# Project.net
KiCad netlist of a schematic drawn in EasyEDA Pro
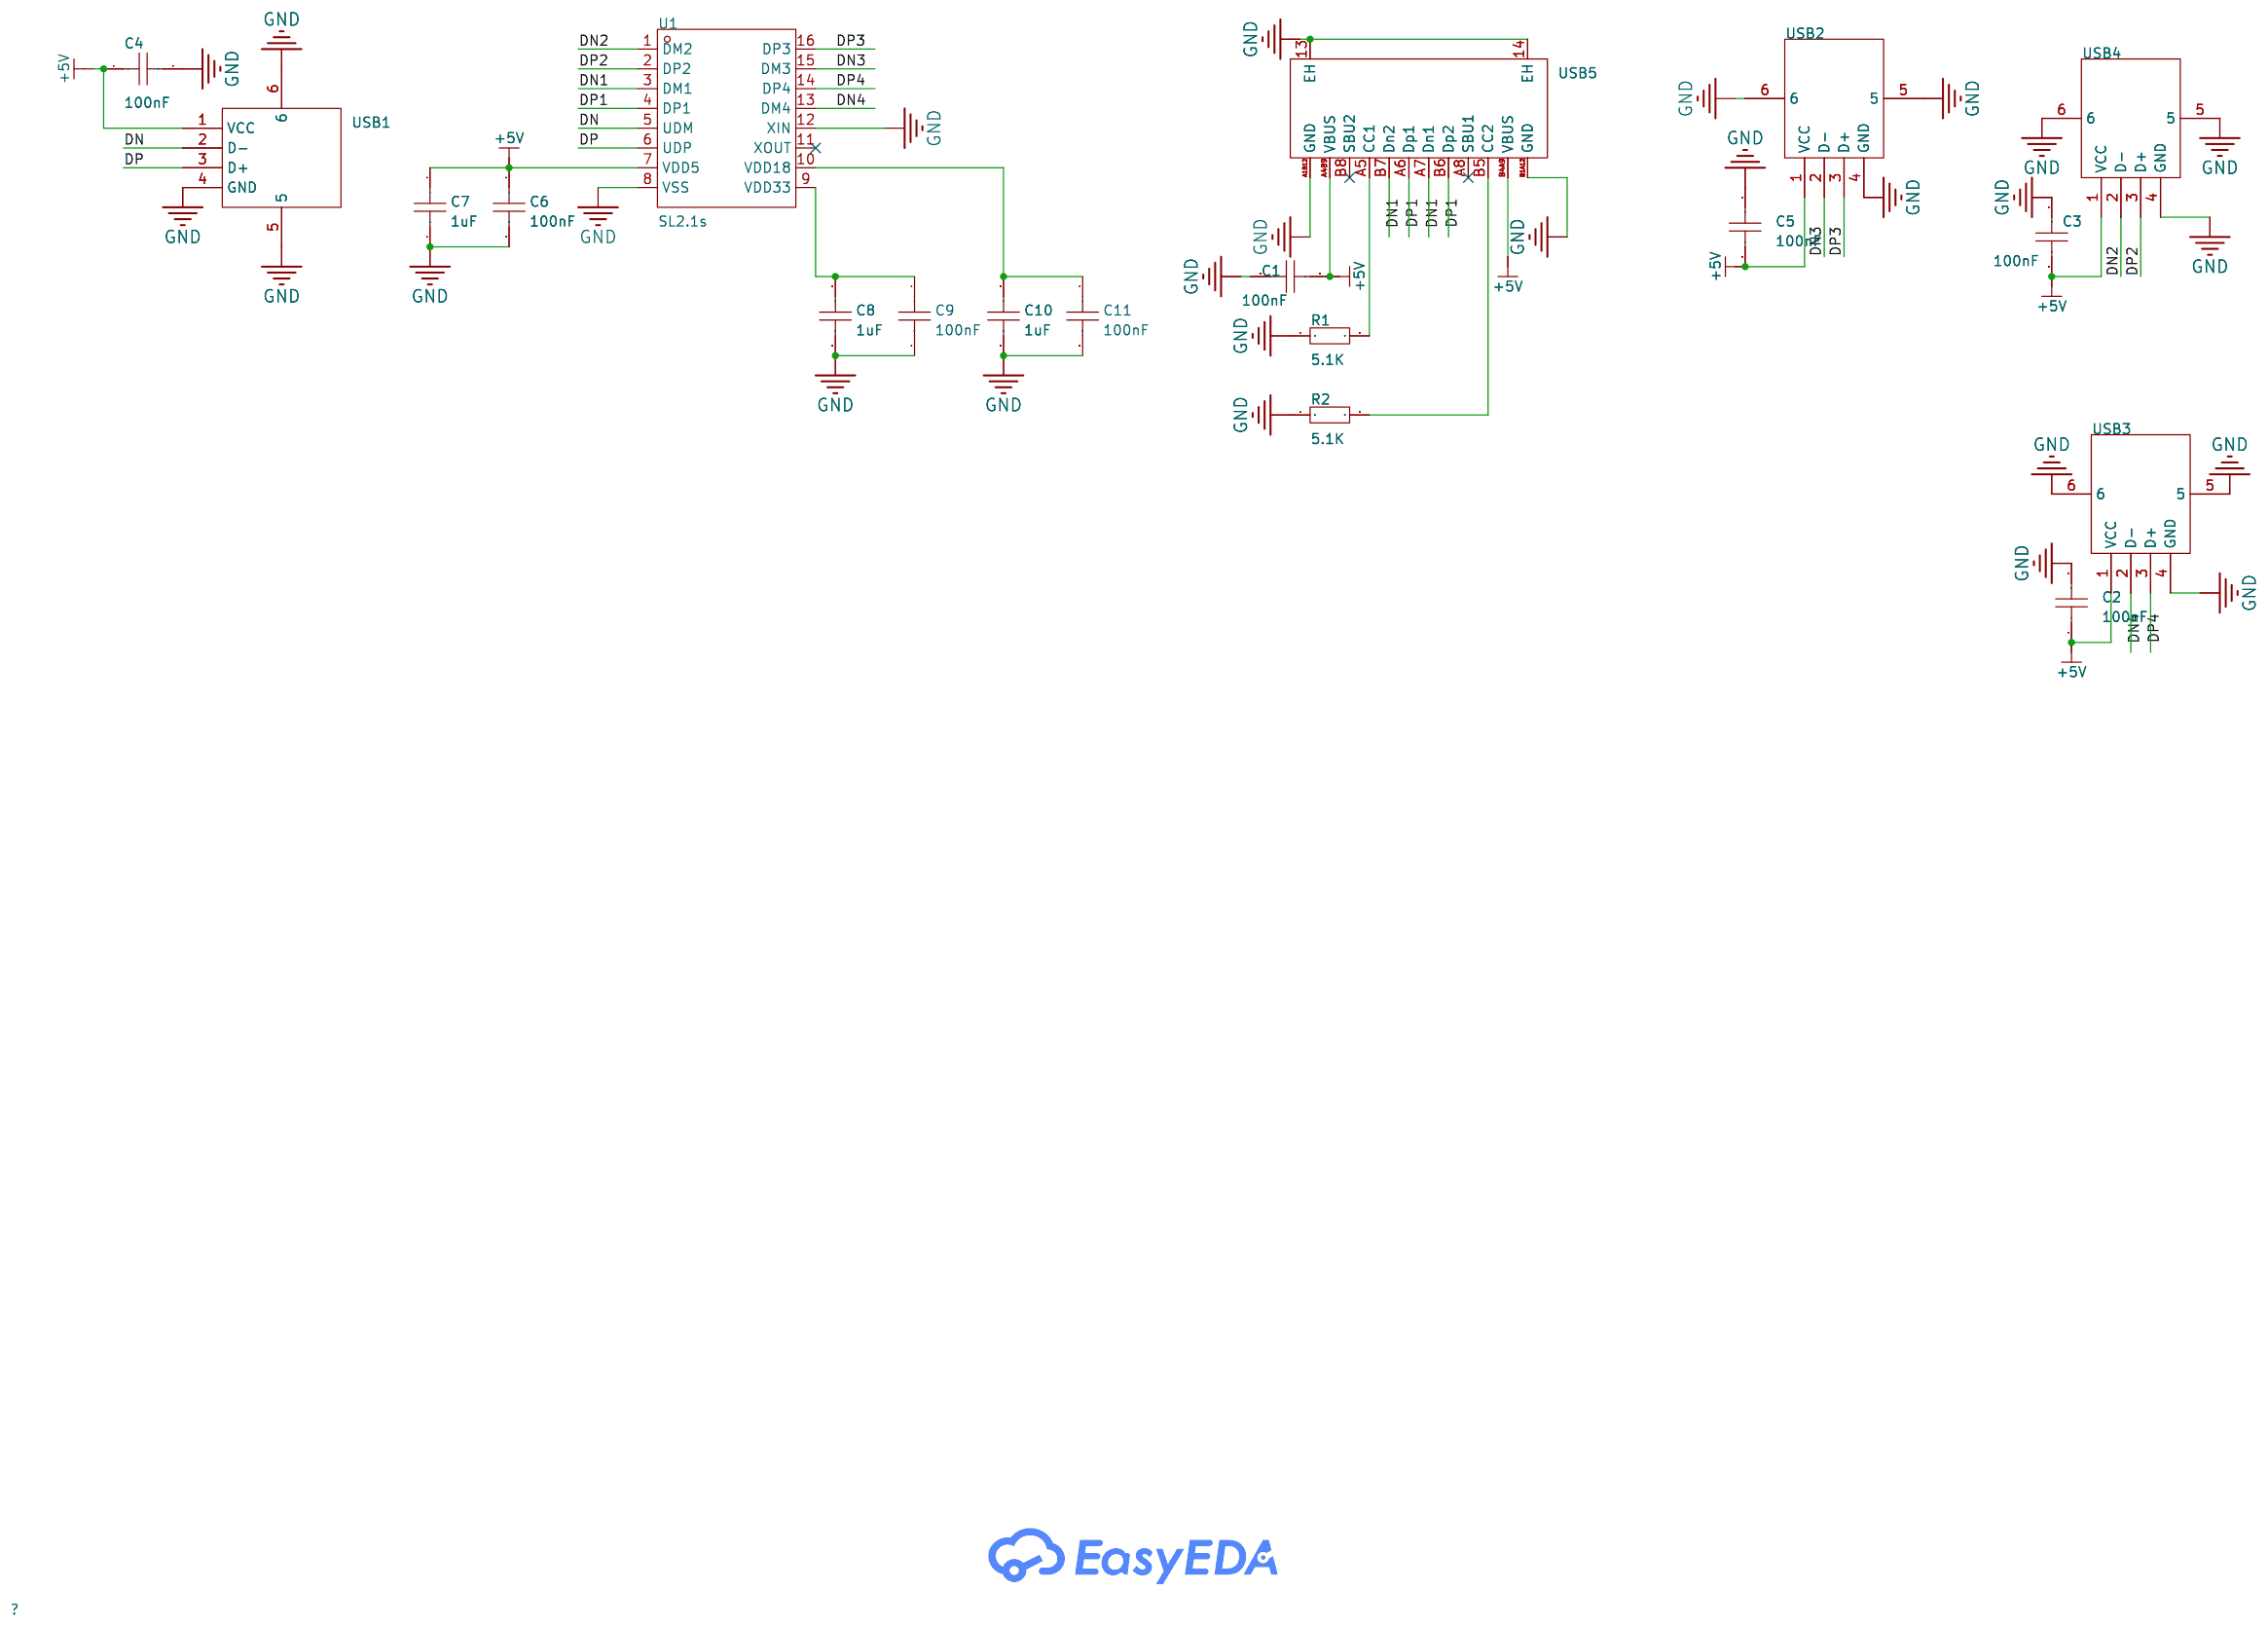
[diagram p0: schematic sheet]

(export (version "E")
  (design (tool "Eeschema 10.0.6"))
  (components
    (comp (ref "C1")
      (value "100nF")
      (footprint "easyedapro:C0603")
      (libsource (lib "easyedapro") (part "CAP"))
    )
    (comp (ref "C2")
      (value "100nF")
      (footprint "easyedapro:C0603")
      (libsource (lib "easyedapro") (part "CAP"))
    )
    (comp (ref "C3")
      (value "100nF")
      (footprint "easyedapro:C0603")
      (libsource (lib "easyedapro") (part "CAP"))
    )
    (comp (ref "C4")
      (value "100nF")
      (footprint "easyedapro:C0603")
      (libsource (lib "easyedapro") (part "CAP"))
    )
    (comp (ref "C5")
      (value "100nF")
      (footprint "easyedapro:C0603")
      (libsource (lib "easyedapro") (part "CAP"))
    )
    (comp (ref "C6")
      (value "100nF")
      (footprint "easyedapro:C0603")
      (libsource (lib "easyedapro") (part "CAP"))
    )
    (comp (ref "C7") (value "1uF") (footprint "easyedapro:C0603") (libsource (lib "easyedapro") (part "CAP")))
    (comp (ref "C8") (value "1uF") (footprint "easyedapro:C0603") (libsource (lib "easyedapro") (part "CAP")))
    (comp (ref "C9")
      (value "100nF")
      (footprint "easyedapro:C0603")
      (libsource (lib "easyedapro") (part "CAP"))
    )
    (comp (ref "C10")
      (value "1uF")
      (footprint "easyedapro:C0603")
      (libsource (lib "easyedapro") (part "CAP"))
    )
    (comp (ref "C11")
      (value "100nF")
      (footprint "easyedapro:C0603")
      (libsource (lib "easyedapro") (part "CAP"))
    )
    (comp (ref "R1")
      (value "5.1K")
      (footprint "easyedapro:R0603")
      (libsource (lib "easyedapro") (part "Res"))
    )
    (comp (ref "R2")
      (value "5.1K")
      (footprint "easyedapro:R0603")
      (libsource (lib "easyedapro") (part "Res"))
    )
    (comp (ref "U1")
      (value "SL2.1s")
      (footprint "easyedapro:SSOP-16_L4.6-W2.6-P0.53-LS4.0-BL")
      (fields (field (name "Manufacturer") "CoreChips(和芯润德)"))
      (libsource (lib "easyedapro") (part "SL2.1S"))
    )
    (comp (ref "USB1")
      (value "10.0 QHHTZB6.3")
      (footprint "easyedapro:USB-A-TH_10.0QHHTZB6.3")
      (fields (field (name "Manufacturer") "SHOU HAN(首韩)"))
      (libsource (lib "easyedapro") (part "10.0 QHHTZB6.3"))
    )
    (comp (ref "USB2")
      (value "10.0 QHHTZB6.3")
      (footprint "easyedapro:USB-A-TH_10.0QHHTZB6.3")
      (fields (field (name "Manufacturer") "SHOU HAN(首韩)"))
      (libsource (lib "easyedapro") (part "10.0 QHHTZB6.3"))
    )
    (comp (ref "USB3")
      (value "10.0 QHHTZB6.3")
      (footprint "easyedapro:USB-A-TH_10.0QHHTZB6.3")
      (fields (field (name "Manufacturer") "SHOU HAN(首韩)"))
      (libsource (lib "easyedapro") (part "10.0 QHHTZB6.3"))
    )
    (comp (ref "USB4")
      (value "10.0 QHHTZB6.3")
      (footprint "easyedapro:USB-A-TH_10.0QHHTZB6.3")
      (fields (field (name "Manufacturer") "SHOU HAN(首韩)"))
      (libsource (lib "easyedapro") (part "10.0 QHHTZB6.3"))
    )
    (comp (ref "USB5")
      (value "TYPE-C 16PIN 2MD(073)")
      (footprint "easyedapro:USB-C-SMD_TYPE-C-16PIN-2MD-073")
      (fields (field (name "Manufacturer") "SHOU HAN(首韩)"))
      (libsource (lib "easyedapro") (part "TYPE-C 16PIN 2MD(073)"))
    )
  )
  (nets
    (net (code "1") (name "+5V") (class "Default")
      (node (ref "C1") (pin "1") (pinfunction "1_1") (pintype "input"))
      (node (ref "C2") (pin "1") (pinfunction "1_1") (pintype "input"))
      (node (ref "C3") (pin "2") (pinfunction "2_2") (pintype "input"))
      (node (ref "C4") (pin "1") (pinfunction "1_1") (pintype "input"))
      (node (ref "C5") (pin "2") (pinfunction "2_2") (pintype "input"))
      (node (ref "C6") (pin "1") (pinfunction "1_1") (pintype "input"))
      (node (ref "C7") (pin "1") (pinfunction "1_1") (pintype "input"))
      (node (ref "U1") (pin "7") (pinfunction "VDD5_7") (pintype "unspecified"))
      (node (ref "USB1") (pin "1") (pinfunction "VCC_1") (pintype "unspecified"))
      (node (ref "USB2") (pin "1") (pinfunction "VCC_1") (pintype "unspecified"))
      (node (ref "USB3") (pin "1") (pinfunction "VCC_1") (pintype "unspecified"))
      (node (ref "USB4") (pin "1") (pinfunction "VCC_1") (pintype "unspecified"))
      (node (ref "USB5") (pin "A4B9") (pinfunction "VBUS_A4B9") (pintype "unspecified"))
      (node (ref "USB5") (pin "B4A9") (pinfunction "VBUS_B4A9") (pintype "unspecified"))
    )
    (net (code "2") (name "/DN") (class "Default")
      (node (ref "U1") (pin "5") (pinfunction "UDM_5") (pintype "unspecified"))
      (node (ref "USB1") (pin "2") (pinfunction "D-_2") (pintype "unspecified"))
    )
    (net (code "3") (name "/DN1") (class "Default")
      (node (ref "U1") (pin "3") (pinfunction "DM1_3") (pintype "unspecified"))
      (node (ref "USB5") (pin "A7") (pinfunction "Dn1_A7") (pintype "unspecified"))
      (node (ref "USB5") (pin "B7") (pinfunction "Dn2_B7") (pintype "unspecified"))
    )
    (net (code "4") (name "/DN2") (class "Default")
      (node (ref "U1") (pin "1") (pinfunction "DM2_1") (pintype "unspecified"))
      (node (ref "USB4") (pin "2") (pinfunction "D-_2") (pintype "unspecified"))
    )
    (net (code "5") (name "/DN3") (class "Default")
      (node (ref "U1") (pin "15") (pinfunction "DM3_15") (pintype "unspecified"))
      (node (ref "USB2") (pin "2") (pinfunction "D-_2") (pintype "unspecified"))
    )
    (net (code "6") (name "/DN4") (class "Default")
      (node (ref "U1") (pin "13") (pinfunction "DM4_13") (pintype "unspecified"))
      (node (ref "USB3") (pin "2") (pinfunction "D-_2") (pintype "unspecified"))
    )
    (net (code "7") (name "/DP") (class "Default")
      (node (ref "U1") (pin "6") (pinfunction "UDP_6") (pintype "unspecified"))
      (node (ref "USB1") (pin "3") (pinfunction "D+_3") (pintype "unspecified"))
    )
    (net (code "8") (name "/DP1") (class "Default")
      (node (ref "U1") (pin "4") (pinfunction "DP1_4") (pintype "unspecified"))
      (node (ref "USB5") (pin "A6") (pinfunction "Dp1_A6") (pintype "unspecified"))
      (node (ref "USB5") (pin "B6") (pinfunction "Dp2_B6") (pintype "unspecified"))
    )
    (net (code "9") (name "/DP2") (class "Default")
      (node (ref "U1") (pin "2") (pinfunction "DP2_2") (pintype "unspecified"))
      (node (ref "USB4") (pin "3") (pinfunction "D+_3") (pintype "unspecified"))
    )
    (net (code "10") (name "/DP3") (class "Default")
      (node (ref "U1") (pin "16") (pinfunction "DP3_16") (pintype "unspecified"))
      (node (ref "USB2") (pin "3") (pinfunction "D+_3") (pintype "unspecified"))
    )
    (net (code "11") (name "/DP4") (class "Default")
      (node (ref "U1") (pin "14") (pinfunction "DP4_14") (pintype "unspecified"))
      (node (ref "USB3") (pin "3") (pinfunction "D+_3") (pintype "unspecified"))
    )
    (net (code "12") (name "GND") (class "Default")
      (node (ref "C1") (pin "2") (pinfunction "2_2") (pintype "input"))
      (node (ref "C10") (pin "2") (pinfunction "2_2") (pintype "input"))
      (node (ref "C11") (pin "2") (pinfunction "2_2") (pintype "input"))
      (node (ref "C2") (pin "2") (pinfunction "2_2") (pintype "input"))
      (node (ref "C3") (pin "1") (pinfunction "1_1") (pintype "input"))
      (node (ref "C4") (pin "2") (pinfunction "2_2") (pintype "input"))
      (node (ref "C5") (pin "1") (pinfunction "1_1") (pintype "input"))
      (node (ref "C6") (pin "2") (pinfunction "2_2") (pintype "input"))
      (node (ref "C7") (pin "2") (pinfunction "2_2") (pintype "input"))
      (node (ref "C8") (pin "2") (pinfunction "2_2") (pintype "input"))
      (node (ref "C9") (pin "2") (pinfunction "2_2") (pintype "input"))
      (node (ref "R1") (pin "1") (pinfunction "1_1") (pintype "input"))
      (node (ref "R2") (pin "1") (pinfunction "1_1") (pintype "input"))
      (node (ref "U1") (pin "12") (pinfunction "XIN_12") (pintype "unspecified"))
      (node (ref "U1") (pin "8") (pinfunction "VSS_8") (pintype "unspecified"))
      (node (ref "USB1") (pin "4") (pinfunction "GND_4") (pintype "unspecified"))
      (node (ref "USB1") (pin "5") (pinfunction "5_5") (pintype "unspecified"))
      (node (ref "USB1") (pin "6") (pinfunction "6_6") (pintype "unspecified"))
      (node (ref "USB2") (pin "4") (pinfunction "GND_4") (pintype "unspecified"))
      (node (ref "USB2") (pin "5") (pinfunction "5_5") (pintype "unspecified"))
      (node (ref "USB2") (pin "6") (pinfunction "6_6") (pintype "unspecified"))
      (node (ref "USB3") (pin "4") (pinfunction "GND_4") (pintype "unspecified"))
      (node (ref "USB3") (pin "5") (pinfunction "5_5") (pintype "unspecified"))
      (node (ref "USB3") (pin "6") (pinfunction "6_6") (pintype "unspecified"))
      (node (ref "USB4") (pin "4") (pinfunction "GND_4") (pintype "unspecified"))
      (node (ref "USB4") (pin "5") (pinfunction "5_5") (pintype "unspecified"))
      (node (ref "USB4") (pin "6") (pinfunction "6_6") (pintype "unspecified"))
      (node (ref "USB5") (pin "13") (pinfunction "EH_13") (pintype "unspecified"))
      (node (ref "USB5") (pin "14") (pinfunction "EH_14") (pintype "unspecified"))
      (node (ref "USB5") (pin "A1B12") (pinfunction "GND_A1B12") (pintype "unspecified"))
      (node (ref "USB5") (pin "B1A12") (pinfunction "GND_B1A12") (pintype "unspecified"))
    )
    (net (code "13") (name "Net-(U1-VDD18)") (class "Default")
      (node (ref "C10") (pin "1") (pinfunction "1_1") (pintype "input"))
      (node (ref "C11") (pin "1") (pinfunction "1_1") (pintype "input"))
      (node (ref "U1") (pin "10") (pinfunction "VDD18_10") (pintype "unspecified"))
    )
    (net (code "14") (name "Net-(U1-VDD33)") (class "Default")
      (node (ref "C8") (pin "1") (pinfunction "1_1") (pintype "input"))
      (node (ref "C9") (pin "1") (pinfunction "1_1") (pintype "input"))
      (node (ref "U1") (pin "9") (pinfunction "VDD33_9") (pintype "unspecified"))
    )
    (net (code "15") (name "Net-(USB5-CC1)") (class "Default")
      (node (ref "R1") (pin "2") (pinfunction "2_2") (pintype "input"))
      (node (ref "USB5") (pin "A5") (pinfunction "CC1_A5") (pintype "unspecified"))
    )
    (net (code "16") (name "Net-(USB5-CC2)") (class "Default")
      (node (ref "R2") (pin "2") (pinfunction "2_2") (pintype "input"))
      (node (ref "USB5") (pin "B5") (pinfunction "CC2_B5") (pintype "unspecified"))
    )
    (net (code "17") (name "unconnected-(U1-XOUT-Pad11)") (class "Default")
      (node (ref "U1") (pin "11") (pinfunction "XOUT_11") (pintype "unspecified+no_connect"))
    )
    (net (code "18") (name "unconnected-(USB5-SBU1-PadA8)") (class "Default")
      (node (ref "USB5") (pin "A8") (pinfunction "SBU1_A8") (pintype "unspecified+no_connect"))
    )
    (net (code "19") (name "unconnected-(USB5-SBU2-PadB8)") (class "Default")
      (node (ref "USB5") (pin "B8") (pinfunction "SBU2_B8") (pintype "unspecified+no_connect"))
    )
  )
)
